# 07_Wireless_Communication.net
KiCad netlist of a schematic drawn in Altium Designer
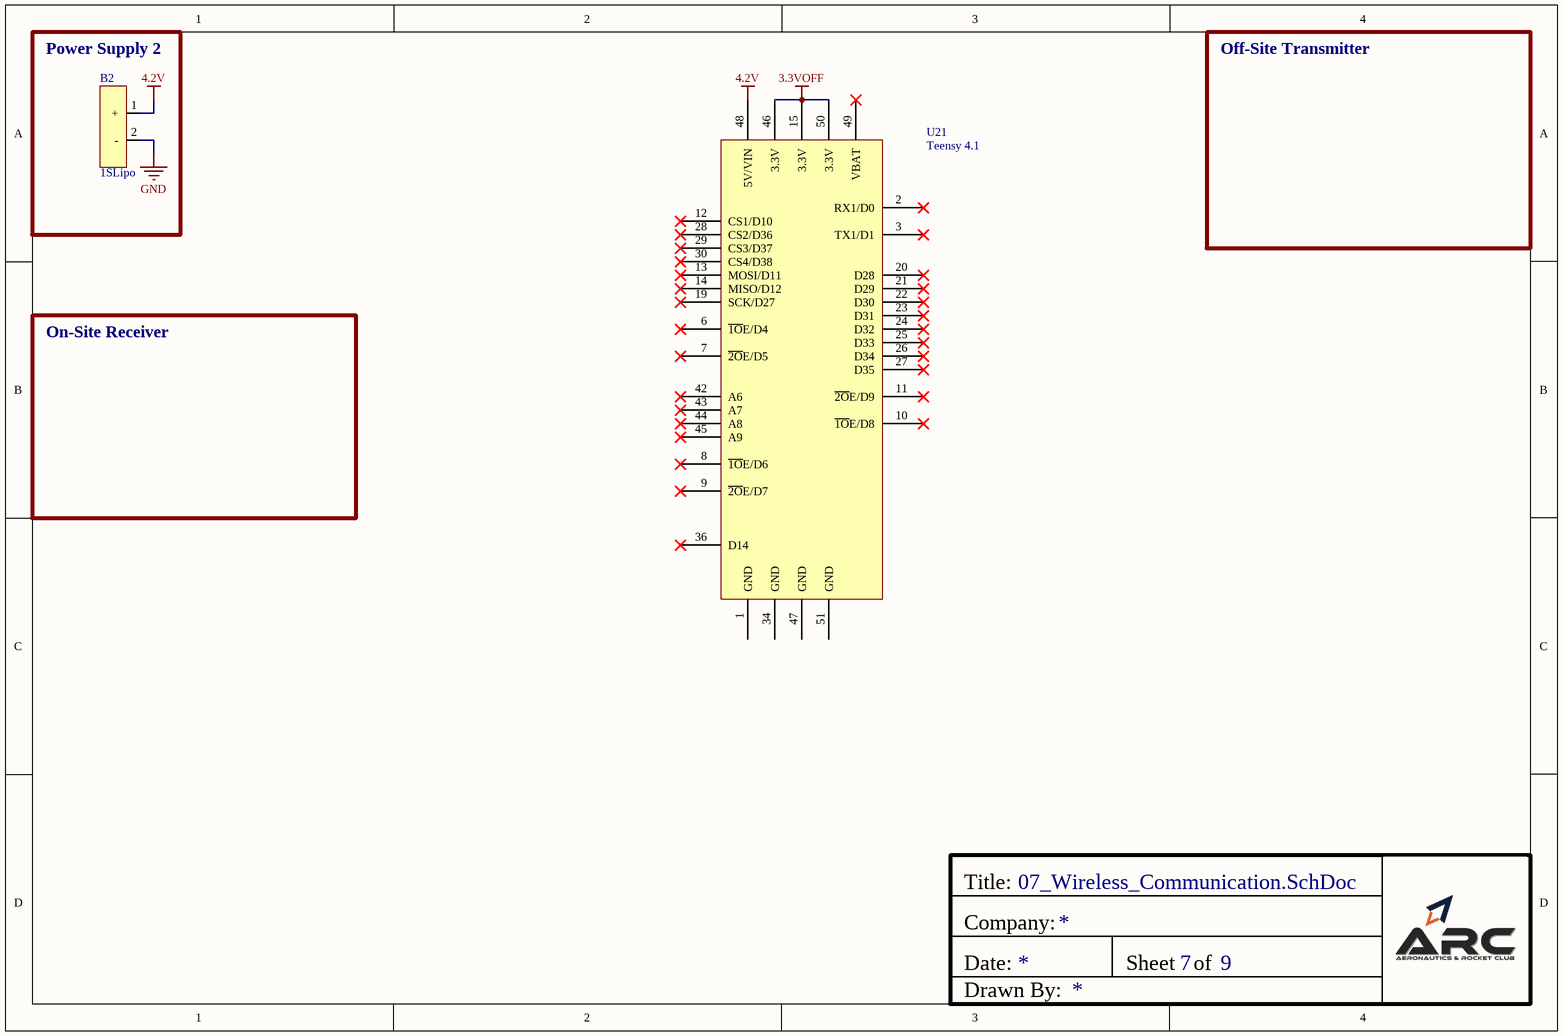
[diagram p0: 07_Wireless_Communication.SchDoc]

(export (version "E")
  (design (tool "Eeschema 10.0.6"))
  (components
    (comp (ref "B2")
      (value "1SLipo")
      (footprint "1SLiPo")
      (libsource (lib "Ground Support_Schlib") (part "1SLiPo"))
    )
    (comp (ref "U21")
      (value "Teensy 4.1")
      (footprint "Teensy 4.1")
      (fields (field (name "MANUFACTURER") "SparkFun") (field (name "MANUFACTURER PART NUMBER") "DEV-16996"))
      (libsource (lib "Ground Support_Schlib") (part "Teensy 4.1"))
    )
  )
  (nets
    (net (code "1") (name "3.3VOFF") (class "Default")
      (node (ref "U21") (pin "15") (pinfunction "3.3V_15") (pintype "passive"))
      (node (ref "U21") (pin "46") (pinfunction "3.3V_46") (pintype "passive"))
      (node (ref "U21") (pin "50") (pinfunction "3.3V_50") (pintype "passive"))
    )
    (net (code "2") (name "4.2V") (class "Default")
      (node (ref "B2") (pin "1") (pinfunction "+_1") (pintype "power_in"))
      (node (ref "U21") (pin "48") (pinfunction "5V/VIN_48") (pintype "passive"))
    )
    (net (code "3") (name "GND") (class "Default")
      (node (ref "B2") (pin "2") (pinfunction "-_2") (pintype "power_in"))
    )
    (net (code "4") (name "unconnected-(U21-A6-Pad42)") (class "Default")
      (node (ref "U21") (pin "42") (pinfunction "A6_42") (pintype "passive+no_connect"))
    )
    (net (code "5") (name "unconnected-(U21-A7-Pad43)") (class "Default")
      (node (ref "U21") (pin "43") (pinfunction "A7_43") (pintype "passive+no_connect"))
    )
    (net (code "6") (name "unconnected-(U21-A8-Pad44)") (class "Default")
      (node (ref "U21") (pin "44") (pinfunction "A8_44") (pintype "passive+no_connect"))
    )
    (net (code "7") (name "unconnected-(U21-A9-Pad45)") (class "Default")
      (node (ref "U21") (pin "45") (pinfunction "A9_45") (pintype "passive+no_connect"))
    )
    (net (code "8") (name "unconnected-(U21-CS1{slash}D10-Pad12)") (class "Default")
      (node (ref "U21") (pin "12") (pinfunction "CS1/D10_12") (pintype "passive+no_connect"))
    )
    (net (code "9") (name "unconnected-(U21-CS2{slash}D36-Pad28)") (class "Default")
      (node (ref "U21") (pin "28") (pinfunction "CS2/D36_28") (pintype "passive+no_connect"))
    )
    (net (code "10") (name "unconnected-(U21-CS3{slash}D37-Pad29)") (class "Default")
      (node (ref "U21") (pin "29") (pinfunction "CS3/D37_29") (pintype "passive+no_connect"))
    )
    (net (code "11") (name "unconnected-(U21-CS4{slash}D38-Pad30)") (class "Default")
      (node (ref "U21") (pin "30") (pinfunction "CS4/D38_30") (pintype "passive+no_connect"))
    )
    (net (code "12") (name "unconnected-(U21-D14-Pad36)") (class "Default")
      (node (ref "U21") (pin "36") (pinfunction "D14_36") (pintype "passive+no_connect"))
    )
    (net (code "13") (name "unconnected-(U21-D28-Pad20)") (class "Default")
      (node (ref "U21") (pin "20") (pinfunction "D28_20") (pintype "passive+no_connect"))
    )
    (net (code "14") (name "unconnected-(U21-D29-Pad21)") (class "Default")
      (node (ref "U21") (pin "21") (pinfunction "D29_21") (pintype "passive+no_connect"))
    )
    (net (code "15") (name "unconnected-(U21-D30-Pad22)") (class "Default")
      (node (ref "U21") (pin "22") (pinfunction "D30_22") (pintype "passive+no_connect"))
    )
    (net (code "16") (name "unconnected-(U21-D31-Pad23)") (class "Default")
      (node (ref "U21") (pin "23") (pinfunction "D31_23") (pintype "passive+no_connect"))
    )
    (net (code "17") (name "unconnected-(U21-D32-Pad24)") (class "Default")
      (node (ref "U21") (pin "24") (pinfunction "D32_24") (pintype "passive+no_connect"))
    )
    (net (code "18") (name "unconnected-(U21-D33-Pad25)") (class "Default")
      (node (ref "U21") (pin "25") (pinfunction "D33_25") (pintype "passive+no_connect"))
    )
    (net (code "19") (name "unconnected-(U21-D34-Pad26)") (class "Default")
      (node (ref "U21") (pin "26") (pinfunction "D34_26") (pintype "passive+no_connect"))
    )
    (net (code "20") (name "unconnected-(U21-D35-Pad27)") (class "Default")
      (node (ref "U21") (pin "27") (pinfunction "D35_27") (pintype "passive+no_connect"))
    )
    (net (code "21") (name "unconnected-(U21-GND-Pad1)") (class "Default")
      (node (ref "U21") (pin "1") (pinfunction "GND_1") (pintype "passive"))
    )
    (net (code "22") (name "unconnected-(U21-GND-Pad34)") (class "Default")
      (node (ref "U21") (pin "34") (pinfunction "GND_34") (pintype "passive"))
    )
    (net (code "23") (name "unconnected-(U21-GND-Pad47)") (class "Default")
      (node (ref "U21") (pin "47") (pinfunction "GND_47") (pintype "passive"))
    )
    (net (code "24") (name "unconnected-(U21-GND-Pad51)") (class "Default")
      (node (ref "U21") (pin "51") (pinfunction "GND_51") (pintype "passive"))
    )
    (net (code "25") (name "unconnected-(U21-MISO{slash}D12-Pad14)") (class "Default")
      (node (ref "U21") (pin "14") (pinfunction "MISO/D12_14") (pintype "passive+no_connect"))
    )
    (net (code "26") (name "unconnected-(U21-MOSI{slash}D11-Pad13)") (class "Default")
      (node (ref "U21") (pin "13") (pinfunction "MOSI/D11_13") (pintype "passive+no_connect"))
    )
    (net (code "27") (name "unconnected-(U21-RX1{slash}D0-Pad2)") (class "Default")
      (node (ref "U21") (pin "2") (pinfunction "RX1/D0_2") (pintype "passive+no_connect"))
    )
    (net (code "28") (name "unconnected-(U21-SCK{slash}D27-Pad19)") (class "Default")
      (node (ref "U21") (pin "19") (pinfunction "SCK/D27_19") (pintype "passive+no_connect"))
    )
    (net (code "29") (name "unconnected-(U21-TX1{slash}D1-Pad3)") (class "Default")
      (node (ref "U21") (pin "3") (pinfunction "TX1/D1_3") (pintype "passive+no_connect"))
    )
    (net (code "30") (name "unconnected-(U21-VBAT-Pad49)") (class "Default")
      (node (ref "U21") (pin "49") (pinfunction "VBAT_49") (pintype "passive+no_connect"))
    )
    (net (code "31") (name "unconnected-(U21-~{1O}E{slash}D4-Pad6)") (class "Default")
      (node (ref "U21") (pin "6") (pinfunction "~{1O}E/D4_6") (pintype "passive+no_connect"))
    )
    (net (code "32") (name "unconnected-(U21-~{1O}E{slash}D6-Pad8)") (class "Default")
      (node (ref "U21") (pin "8") (pinfunction "~{1O}E/D6_8") (pintype "passive+no_connect"))
    )
    (net (code "33") (name "unconnected-(U21-~{1O}E{slash}D8-Pad10)") (class "Default")
      (node (ref "U21") (pin "10") (pinfunction "~{1O}E/D8_10") (pintype "passive+no_connect"))
    )
    (net (code "34") (name "unconnected-(U21-~{2O}E{slash}D5-Pad7)") (class "Default")
      (node (ref "U21") (pin "7") (pinfunction "~{2O}E/D5_7") (pintype "passive+no_connect"))
    )
    (net (code "35") (name "unconnected-(U21-~{2O}E{slash}D7-Pad9)") (class "Default")
      (node (ref "U21") (pin "9") (pinfunction "~{2O}E/D7_9") (pintype "passive+no_connect"))
    )
    (net (code "36") (name "unconnected-(U21-~{2O}E{slash}D9-Pad11)") (class "Default")
      (node (ref "U21") (pin "11") (pinfunction "~{2O}E/D9_11") (pintype "passive+no_connect"))
    )
  )
)
